# sensor-1.net
KiCad netlist of a schematic drawn in Altium Designer
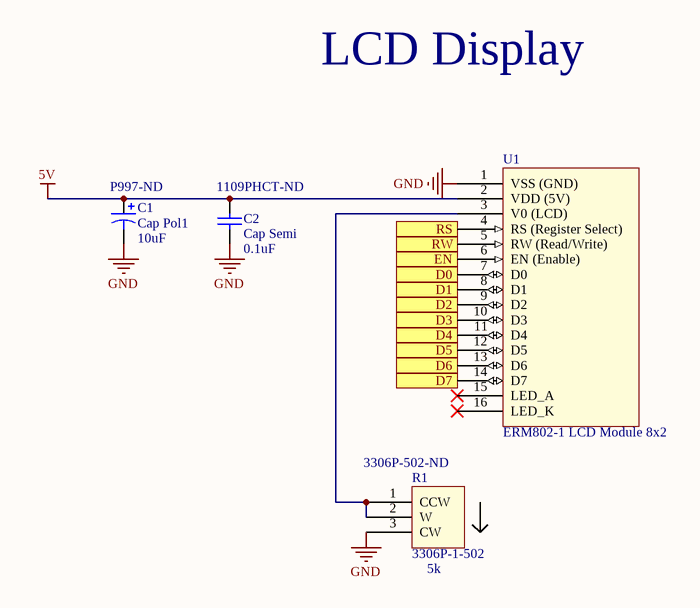
[diagram p0: sensor-1.SchDoc]

(export (version "E")
  (design (tool "Eeschema 10.0.6"))
  (components
    (comp (ref "C1")
      (value "Cap Pol1")
      (footprint "ECE-A1HKS100")
      (description "Polarized Capacitor (Radial)")
      (fields
        (field (name "ALTIUM_VALUE") "10uF")
        (field (name "SUPPLIER PART NUMBER 1") "P997-ND")
        (field (name "MANUFACTURER") "Panasonic")
        (field (name "MANUFACTURER PART NUMBER") "ECE-A1HKS100")
        (field (name "PUBLISHER") "Altium Limited")
      )
      (libsource (lib "Miscellaneous Devices") (part "Cap Pol1"))
    )
    (comp (ref "C2")
      (value "Cap Semi")
      (footprint "A104K15X7RF5TAA")
      (description "Capacitor (Semiconductor SIM Model)")
      (fields
        (field (name "ALTIUM_VALUE") "0.1uF")
        (field (name "SUPPLIER PART NUMBER 1") "1109PHCT-ND")
        (field (name "MANUFACTURER") "Vishay BCcomponents")
        (field (name "MANUFACTURER PART NUMBER") "A104K15X7RF5TAA")
        (field (name "PUBLISHER") "Altium Limited")
      )
      (libsource (lib "Miscellaneous Devices") (part "Cap Semi"))
    )
    (comp (ref "R1")
      (value "3306P-1-502")
      (footprint "3306P-1-502")
      (description "TRIMMER 5K OHM 0.2W PC PIN TOP")
      (fields
        (field (name "SUPPLIER PART NUMBER 1") "3306P-502-ND")
        (field (name "MANUFACTURER") "Bourns")
        (field (name "TOLERANCE") "25%")
      )
      (libsource (lib "bourns") (part "3306P-1-502"))
    )
    (comp (ref "U1")
      (value "ERM802-1 LCD Module 8x2")
      (footprint "ERM802-1")
      (libsource (lib "EastRising") (part "ERM802-1"))
    )
  )
  (nets
    (net (code "1") (name "/D0") (class "Default")
      (node (ref "U1") (pin "7") (pinfunction "D0_7") (pintype "bidirectional"))
    )
    (net (code "2") (name "/D1") (class "Default")
      (node (ref "U1") (pin "8") (pinfunction "D1_8") (pintype "bidirectional"))
    )
    (net (code "3") (name "/D2") (class "Default")
      (node (ref "U1") (pin "9") (pinfunction "D2_9") (pintype "bidirectional"))
    )
    (net (code "4") (name "/D3") (class "Default")
      (node (ref "U1") (pin "10") (pinfunction "D3_10") (pintype "bidirectional"))
    )
    (net (code "5") (name "/D4") (class "Default")
      (node (ref "U1") (pin "11") (pinfunction "D4_11") (pintype "bidirectional"))
    )
    (net (code "6") (name "/D5") (class "Default")
      (node (ref "U1") (pin "12") (pinfunction "D5_12") (pintype "bidirectional"))
    )
    (net (code "7") (name "/D6") (class "Default")
      (node (ref "U1") (pin "13") (pinfunction "D6_13") (pintype "bidirectional"))
    )
    (net (code "8") (name "/D7") (class "Default")
      (node (ref "U1") (pin "14") (pinfunction "D7_14") (pintype "bidirectional"))
    )
    (net (code "9") (name "/EN") (class "Default")
      (node (ref "U1") (pin "6") (pinfunction "EN_(Enable)_6") (pintype "input"))
    )
    (net (code "10") (name "/RS") (class "Default")
      (node (ref "U1") (pin "4") (pinfunction "RS_(Register_Select)_4") (pintype "input"))
    )
    (net (code "11") (name "/RW") (class "Default")
      (node (ref "U1") (pin "5") (pinfunction "RW_(Read/Write)_5") (pintype "input"))
    )
    (net (code "12") (name "5V") (class "Default")
      (node (ref "C1") (pin "1") (pinfunction "1_1") (pintype "passive"))
      (node (ref "C2") (pin "2") (pinfunction "2_2") (pintype "passive"))
      (node (ref "U1") (pin "2") (pinfunction "VDD_(5V)_2") (pintype "power_in"))
    )
    (net (code "13") (name "GND") (class "Default")
      (node (ref "C1") (pin "2") (pinfunction "2_2") (pintype "passive"))
      (node (ref "C2") (pin "1") (pinfunction "1_1") (pintype "passive"))
      (node (ref "R1") (pin "3") (pinfunction "CW_3") (pintype "passive"))
      (node (ref "U1") (pin "1") (pinfunction "VSS_(GND)_1") (pintype "power_in"))
    )
    (net (code "14") (name "Net-(R1-CCW)") (class "Default")
      (node (ref "R1") (pin "1") (pinfunction "CCW_1") (pintype "passive"))
      (node (ref "R1") (pin "2") (pinfunction "W_2") (pintype "passive"))
      (node (ref "U1") (pin "3") (pinfunction "V0_(LCD)_3") (pintype "power_in"))
    )
    (net (code "15") (name "unconnected-(U1-LED_A-Pad15)") (class "Default")
      (node (ref "U1") (pin "15") (pinfunction "LED_A_15") (pintype "power_in+no_connect"))
    )
    (net (code "16") (name "unconnected-(U1-LED_K-Pad16)") (class "Default")
      (node (ref "U1") (pin "16") (pinfunction "LED_K_16") (pintype "power_in+no_connect"))
    )
  )
)
